# LTC6804-2_12S.net
KiCad netlist of a schematic drawn in Altium Designer
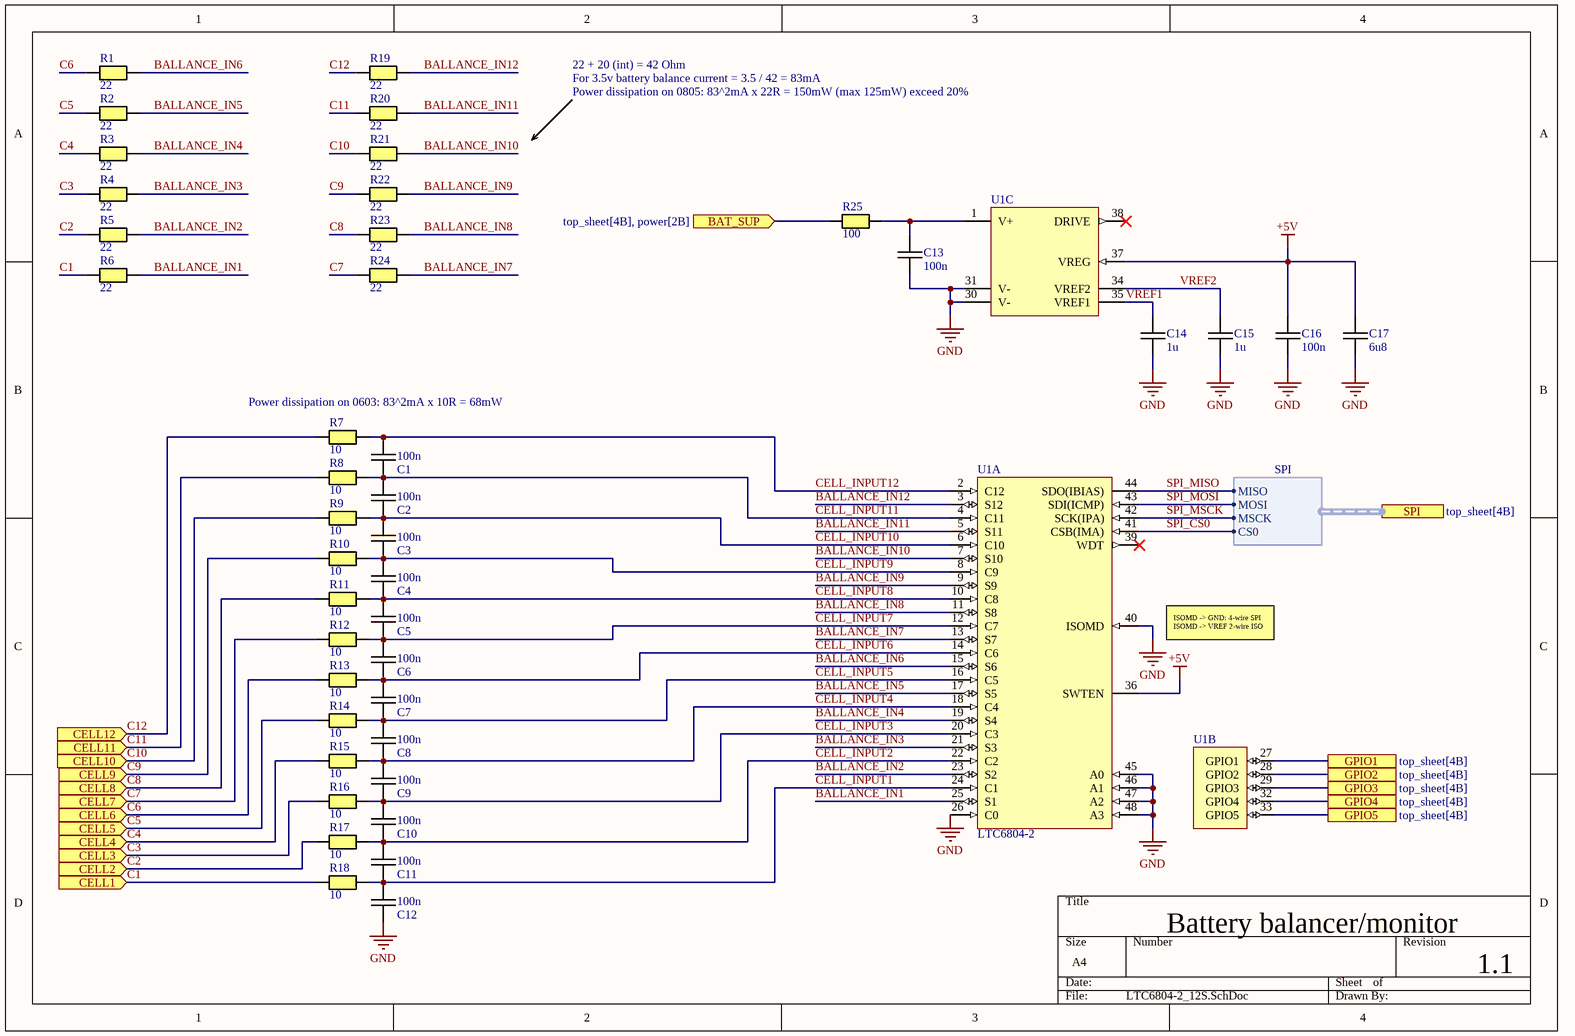
[diagram p0: LTC6804-2_12S.SchDoc]

(export (version "E")
  (design (tool "Eeschema 10.0.6"))
  (components
    (comp (ref "C1")
      (value "100n")
      (footprint "CAPC0603(1608)55_N")
      (description "Ceramic capacitor Medium density")
      (libsource (lib "Discrete") (part "Capacitor M"))
    )
    (comp (ref "C2")
      (value "100n")
      (footprint "CAPC0603(1608)55_N")
      (description "Ceramic capacitor Medium density")
      (libsource (lib "Discrete") (part "Capacitor M"))
    )
    (comp (ref "C3")
      (value "100n")
      (footprint "CAPC0603(1608)55_N")
      (description "Ceramic capacitor Medium density")
      (libsource (lib "Discrete") (part "Capacitor M"))
    )
    (comp (ref "C4")
      (value "100n")
      (footprint "CAPC0603(1608)55_N")
      (description "Ceramic capacitor Medium density")
      (libsource (lib "Discrete") (part "Capacitor M"))
    )
    (comp (ref "C5")
      (value "100n")
      (footprint "CAPC0603(1608)55_N")
      (description "Ceramic capacitor Medium density")
      (libsource (lib "Discrete") (part "Capacitor M"))
    )
    (comp (ref "C6")
      (value "100n")
      (footprint "CAPC0603(1608)55_N")
      (description "Ceramic capacitor Medium density")
      (libsource (lib "Discrete") (part "Capacitor M"))
    )
    (comp (ref "C7")
      (value "100n")
      (footprint "CAPC0603(1608)55_N")
      (description "Ceramic capacitor Medium density")
      (libsource (lib "Discrete") (part "Capacitor M"))
    )
    (comp (ref "C8")
      (value "100n")
      (footprint "CAPC0603(1608)55_N")
      (description "Ceramic capacitor Medium density")
      (libsource (lib "Discrete") (part "Capacitor M"))
    )
    (comp (ref "C9")
      (value "100n")
      (footprint "CAPC0603(1608)55_N")
      (description "Ceramic capacitor Medium density")
      (libsource (lib "Discrete") (part "Capacitor M"))
    )
    (comp (ref "C10")
      (value "100n")
      (footprint "CAPC0603(1608)55_N")
      (description "Ceramic capacitor Medium density")
      (libsource (lib "Discrete") (part "Capacitor M"))
    )
    (comp (ref "C11")
      (value "100n")
      (footprint "CAPC0603(1608)55_N")
      (description "Ceramic capacitor Medium density")
      (libsource (lib "Discrete") (part "Capacitor M"))
    )
    (comp (ref "C12")
      (value "100n")
      (footprint "CAPC0603(1608)55_N")
      (description "Ceramic capacitor Medium density")
      (libsource (lib "Discrete") (part "Capacitor M"))
    )
    (comp (ref "C13")
      (value "100n")
      (footprint "CAPC0603(1608)55_N")
      (description "Ceramic capacitor Medium density")
      (libsource (lib "Discrete") (part "Capacitor M"))
    )
    (comp (ref "C14")
      (value "1u")
      (footprint "CAPC0805(2012)75_N")
      (description "Ceramic capacitor Medium density")
      (libsource (lib "Discrete") (part "Capacitor M"))
    )
    (comp (ref "C15")
      (value "1u")
      (footprint "CAPC0805(2012)75_N")
      (description "Ceramic capacitor Medium density")
      (libsource (lib "Discrete") (part "Capacitor M"))
    )
    (comp (ref "C16")
      (value "100n")
      (footprint "CAPC0603(1608)55_N")
      (description "Ceramic capacitor Medium density")
      (libsource (lib "Discrete") (part "Capacitor M"))
    )
    (comp (ref "C17")
      (value "6u8")
      (footprint "CAPC0805(2012)75_N")
      (description "Ceramic capacitor Medium density")
      (libsource (lib "Discrete") (part "Capacitor M"))
    )
    (comp (ref "R1")
      (value "22")
      (footprint "RESC0805(2012)_N")
      (description "Resistor Medium Density")
      (libsource (lib "Discrete") (part "Resistor M"))
    )
    (comp (ref "R2")
      (value "22")
      (footprint "RESC0805(2012)_N")
      (description "Resistor Medium Density")
      (libsource (lib "Discrete") (part "Resistor M"))
    )
    (comp (ref "R3")
      (value "22")
      (footprint "RESC0805(2012)_N")
      (description "Resistor Medium Density")
      (libsource (lib "Discrete") (part "Resistor M"))
    )
    (comp (ref "R4")
      (value "22")
      (footprint "RESC0805(2012)_N")
      (description "Resistor Medium Density")
      (libsource (lib "Discrete") (part "Resistor M"))
    )
    (comp (ref "R5")
      (value "22")
      (footprint "RESC0805(2012)_N")
      (description "Resistor Medium Density")
      (libsource (lib "Discrete") (part "Resistor M"))
    )
    (comp (ref "R6")
      (value "22")
      (footprint "RESC0805(2012)_N")
      (description "Resistor Medium Density")
      (libsource (lib "Discrete") (part "Resistor M"))
    )
    (comp (ref "R7")
      (value "10")
      (footprint "RESC0603(1608)_N")
      (description "Resistor Medium Density")
      (libsource (lib "Discrete") (part "Resistor M"))
    )
    (comp (ref "R8")
      (value "10")
      (footprint "RESC0603(1608)_N")
      (description "Resistor Medium Density")
      (libsource (lib "Discrete") (part "Resistor M"))
    )
    (comp (ref "R9")
      (value "10")
      (footprint "RESC0603(1608)_N")
      (description "Resistor Medium Density")
      (libsource (lib "Discrete") (part "Resistor M"))
    )
    (comp (ref "R10")
      (value "10")
      (footprint "RESC0603(1608)_N")
      (description "Resistor Medium Density")
      (libsource (lib "Discrete") (part "Resistor M"))
    )
    (comp (ref "R11")
      (value "10")
      (footprint "RESC0603(1608)_N")
      (description "Resistor Medium Density")
      (libsource (lib "Discrete") (part "Resistor M"))
    )
    (comp (ref "R12")
      (value "10")
      (footprint "RESC0603(1608)_N")
      (description "Resistor Medium Density")
      (libsource (lib "Discrete") (part "Resistor M"))
    )
    (comp (ref "R13")
      (value "10")
      (footprint "RESC0603(1608)_N")
      (description "Resistor Medium Density")
      (libsource (lib "Discrete") (part "Resistor M"))
    )
    (comp (ref "R14")
      (value "10")
      (footprint "RESC0603(1608)_N")
      (description "Resistor Medium Density")
      (libsource (lib "Discrete") (part "Resistor M"))
    )
    (comp (ref "R15")
      (value "10")
      (footprint "RESC0603(1608)_N")
      (description "Resistor Medium Density")
      (libsource (lib "Discrete") (part "Resistor M"))
    )
    (comp (ref "R16")
      (value "10")
      (footprint "RESC0603(1608)_N")
      (description "Resistor Medium Density")
      (libsource (lib "Discrete") (part "Resistor M"))
    )
    (comp (ref "R17")
      (value "10")
      (footprint "RESC0603(1608)_N")
      (description "Resistor Medium Density")
      (libsource (lib "Discrete") (part "Resistor M"))
    )
    (comp (ref "R18")
      (value "10")
      (footprint "RESC0603(1608)_N")
      (description "Resistor Medium Density")
      (libsource (lib "Discrete") (part "Resistor M"))
    )
    (comp (ref "R19")
      (value "22")
      (footprint "RESC0805(2012)_N")
      (description "Resistor Medium Density")
      (libsource (lib "Discrete") (part "Resistor M"))
    )
    (comp (ref "R20")
      (value "22")
      (footprint "RESC0805(2012)_N")
      (description "Resistor Medium Density")
      (libsource (lib "Discrete") (part "Resistor M"))
    )
    (comp (ref "R21")
      (value "22")
      (footprint "RESC0805(2012)_N")
      (description "Resistor Medium Density")
      (libsource (lib "Discrete") (part "Resistor M"))
    )
    (comp (ref "R22")
      (value "22")
      (footprint "RESC0805(2012)_N")
      (description "Resistor Medium Density")
      (libsource (lib "Discrete") (part "Resistor M"))
    )
    (comp (ref "R23")
      (value "22")
      (footprint "RESC0805(2012)_N")
      (description "Resistor Medium Density")
      (libsource (lib "Discrete") (part "Resistor M"))
    )
    (comp (ref "R24")
      (value "22")
      (footprint "RESC0805(2012)_N")
      (description "Resistor Medium Density")
      (libsource (lib "Discrete") (part "Resistor M"))
    )
    (comp (ref "R25")
      (value "100")
      (footprint "RESC0603(1608)_N")
      (description "Resistor Medium Density")
      (libsource (lib "Discrete") (part "Resistor M"))
    )
    (comp (ref "U1")
      (value "LTC6804-2")
      (footprint "SSOP48")
      (libsource (lib "IntegrationCircuits") (part "LTC6804-2"))
    )
  )
  (nets
    (net (code "2") (name "+5V") (class "Default")
      (node (ref "C16") (pin "1") (pinfunction "1_1") (pintype "passive"))
      (node (ref "C17") (pin "1") (pinfunction "1_1") (pintype "passive"))
      (node (ref "U1") (pin "36") (pinfunction "SWTEN_36") (pintype "passive"))
      (node (ref "U1") (pin "37") (pinfunction "VREG_37") (pintype "input"))
    )
    (net (code "3") (name "/BALLANCE_IN1") (class "Default")
      (node (ref "R6") (pin "2") (pinfunction "2_2") (pintype "passive"))
      (node (ref "U1") (pin "25") (pinfunction "S1_25") (pintype "bidirectional"))
    )
    (net (code "4") (name "/BALLANCE_IN2") (class "Default")
      (node (ref "R5") (pin "2") (pinfunction "2_2") (pintype "passive"))
      (node (ref "U1") (pin "23") (pinfunction "S2_23") (pintype "bidirectional"))
    )
    (net (code "5") (name "/BALLANCE_IN3") (class "Default")
      (node (ref "R4") (pin "2") (pinfunction "2_2") (pintype "passive"))
      (node (ref "U1") (pin "21") (pinfunction "S3_21") (pintype "bidirectional"))
    )
    (net (code "6") (name "/BALLANCE_IN4") (class "Default")
      (node (ref "R3") (pin "2") (pinfunction "2_2") (pintype "passive"))
      (node (ref "U1") (pin "19") (pinfunction "S4_19") (pintype "bidirectional"))
    )
    (net (code "7") (name "/BALLANCE_IN5") (class "Default")
      (node (ref "R2") (pin "2") (pinfunction "2_2") (pintype "passive"))
      (node (ref "U1") (pin "17") (pinfunction "S5_17") (pintype "bidirectional"))
    )
    (net (code "8") (name "/BALLANCE_IN6") (class "Default")
      (node (ref "R1") (pin "2") (pinfunction "2_2") (pintype "passive"))
      (node (ref "U1") (pin "15") (pinfunction "S6_15") (pintype "bidirectional"))
    )
    (net (code "9") (name "/BALLANCE_IN7") (class "Default")
      (node (ref "R24") (pin "2") (pinfunction "2_2") (pintype "passive"))
      (node (ref "U1") (pin "13") (pinfunction "S7_13") (pintype "bidirectional"))
    )
    (net (code "10") (name "/BALLANCE_IN8") (class "Default")
      (node (ref "R23") (pin "2") (pinfunction "2_2") (pintype "passive"))
      (node (ref "U1") (pin "11") (pinfunction "S8_11") (pintype "bidirectional"))
    )
    (net (code "11") (name "/BALLANCE_IN9") (class "Default")
      (node (ref "R22") (pin "2") (pinfunction "2_2") (pintype "passive"))
      (node (ref "U1") (pin "9") (pinfunction "S9_9") (pintype "bidirectional"))
    )
    (net (code "12") (name "/BALLANCE_IN10") (class "Default")
      (node (ref "R21") (pin "2") (pinfunction "2_2") (pintype "passive"))
      (node (ref "U1") (pin "7") (pinfunction "S10_7") (pintype "bidirectional"))
    )
    (net (code "13") (name "/BALLANCE_IN11") (class "Default")
      (node (ref "R20") (pin "2") (pinfunction "2_2") (pintype "passive"))
      (node (ref "U1") (pin "5") (pinfunction "S11_5") (pintype "bidirectional"))
    )
    (net (code "14") (name "/BALLANCE_IN12") (class "Default")
      (node (ref "R19") (pin "2") (pinfunction "2_2") (pintype "passive"))
      (node (ref "U1") (pin "3") (pinfunction "S12_3") (pintype "bidirectional"))
    )
    (net (code "15") (name "/BAT_SUP") (class "Default")
      (node (ref "R25") (pin "1") (pinfunction "1_1") (pintype "passive"))
    )
    (net (code "16") (name "/C1") (class "Default")
      (node (ref "R18") (pin "1") (pinfunction "1_1") (pintype "passive"))
      (node (ref "R6") (pin "1") (pinfunction "1_1") (pintype "passive"))
    )
    (net (code "17") (name "/C2") (class "Default")
      (node (ref "R17") (pin "1") (pinfunction "1_1") (pintype "passive"))
      (node (ref "R5") (pin "1") (pinfunction "1_1") (pintype "passive"))
    )
    (net (code "18") (name "/C3") (class "Default")
      (node (ref "R16") (pin "1") (pinfunction "1_1") (pintype "passive"))
      (node (ref "R4") (pin "1") (pinfunction "1_1") (pintype "passive"))
    )
    (net (code "19") (name "/C4") (class "Default")
      (node (ref "R15") (pin "1") (pinfunction "1_1") (pintype "passive"))
      (node (ref "R3") (pin "1") (pinfunction "1_1") (pintype "passive"))
    )
    (net (code "20") (name "/C5") (class "Default")
      (node (ref "R14") (pin "1") (pinfunction "1_1") (pintype "passive"))
      (node (ref "R2") (pin "1") (pinfunction "1_1") (pintype "passive"))
    )
    (net (code "21") (name "/C6") (class "Default")
      (node (ref "R1") (pin "1") (pinfunction "1_1") (pintype "passive"))
      (node (ref "R13") (pin "1") (pinfunction "1_1") (pintype "passive"))
    )
    (net (code "22") (name "/C7") (class "Default")
      (node (ref "R12") (pin "1") (pinfunction "1_1") (pintype "passive"))
      (node (ref "R24") (pin "1") (pinfunction "1_1") (pintype "passive"))
    )
    (net (code "23") (name "/C8") (class "Default")
      (node (ref "R11") (pin "1") (pinfunction "1_1") (pintype "passive"))
      (node (ref "R23") (pin "1") (pinfunction "1_1") (pintype "passive"))
    )
    (net (code "24") (name "/C9") (class "Default")
      (node (ref "R10") (pin "1") (pinfunction "1_1") (pintype "passive"))
      (node (ref "R22") (pin "1") (pinfunction "1_1") (pintype "passive"))
    )
    (net (code "25") (name "/C10") (class "Default")
      (node (ref "R21") (pin "1") (pinfunction "1_1") (pintype "passive"))
      (node (ref "R9") (pin "1") (pinfunction "1_1") (pintype "passive"))
    )
    (net (code "26") (name "/C11") (class "Default")
      (node (ref "R20") (pin "1") (pinfunction "1_1") (pintype "passive"))
      (node (ref "R8") (pin "1") (pinfunction "1_1") (pintype "passive"))
    )
    (net (code "27") (name "/C12") (class "Default")
      (node (ref "R19") (pin "1") (pinfunction "1_1") (pintype "passive"))
      (node (ref "R7") (pin "1") (pinfunction "1_1") (pintype "passive"))
    )
    (net (code "28") (name "/CELL_INPUT1") (class "Default")
      (node (ref "C11") (pin "2") (pinfunction "2_2") (pintype "passive"))
      (node (ref "C12") (pin "1") (pinfunction "1_1") (pintype "passive"))
      (node (ref "R18") (pin "2") (pinfunction "2_2") (pintype "passive"))
      (node (ref "U1") (pin "24") (pinfunction "C1_24") (pintype "input"))
    )
    (net (code "29") (name "/CELL_INPUT2") (class "Default")
      (node (ref "C10") (pin "2") (pinfunction "2_2") (pintype "passive"))
      (node (ref "C11") (pin "1") (pinfunction "1_1") (pintype "passive"))
      (node (ref "R17") (pin "2") (pinfunction "2_2") (pintype "passive"))
      (node (ref "U1") (pin "22") (pinfunction "C2_22") (pintype "input"))
    )
    (net (code "30") (name "/CELL_INPUT3") (class "Default")
      (node (ref "C10") (pin "1") (pinfunction "1_1") (pintype "passive"))
      (node (ref "C9") (pin "2") (pinfunction "2_2") (pintype "passive"))
      (node (ref "R16") (pin "2") (pinfunction "2_2") (pintype "passive"))
      (node (ref "U1") (pin "20") (pinfunction "C3_20") (pintype "input"))
    )
    (net (code "31") (name "/CELL_INPUT4") (class "Default")
      (node (ref "C8") (pin "2") (pinfunction "2_2") (pintype "passive"))
      (node (ref "C9") (pin "1") (pinfunction "1_1") (pintype "passive"))
      (node (ref "R15") (pin "2") (pinfunction "2_2") (pintype "passive"))
      (node (ref "U1") (pin "18") (pinfunction "C4_18") (pintype "input"))
    )
    (net (code "32") (name "/CELL_INPUT5") (class "Default")
      (node (ref "C7") (pin "2") (pinfunction "2_2") (pintype "passive"))
      (node (ref "C8") (pin "1") (pinfunction "1_1") (pintype "passive"))
      (node (ref "R14") (pin "2") (pinfunction "2_2") (pintype "passive"))
      (node (ref "U1") (pin "16") (pinfunction "C5_16") (pintype "input"))
    )
    (net (code "33") (name "/CELL_INPUT6") (class "Default")
      (node (ref "C6") (pin "2") (pinfunction "2_2") (pintype "passive"))
      (node (ref "C7") (pin "1") (pinfunction "1_1") (pintype "passive"))
      (node (ref "R13") (pin "2") (pinfunction "2_2") (pintype "passive"))
      (node (ref "U1") (pin "14") (pinfunction "C6_14") (pintype "input"))
    )
    (net (code "34") (name "/CELL_INPUT7") (class "Default")
      (node (ref "C5") (pin "2") (pinfunction "2_2") (pintype "passive"))
      (node (ref "C6") (pin "1") (pinfunction "1_1") (pintype "passive"))
      (node (ref "R12") (pin "2") (pinfunction "2_2") (pintype "passive"))
      (node (ref "U1") (pin "12") (pinfunction "C7_12") (pintype "input"))
    )
    (net (code "35") (name "/CELL_INPUT8") (class "Default")
      (node (ref "C4") (pin "2") (pinfunction "2_2") (pintype "passive"))
      (node (ref "C5") (pin "1") (pinfunction "1_1") (pintype "passive"))
      (node (ref "R11") (pin "2") (pinfunction "2_2") (pintype "passive"))
      (node (ref "U1") (pin "10") (pinfunction "C8_10") (pintype "input"))
    )
    (net (code "36") (name "/CELL_INPUT9") (class "Default")
      (node (ref "C3") (pin "2") (pinfunction "2_2") (pintype "passive"))
      (node (ref "C4") (pin "1") (pinfunction "1_1") (pintype "passive"))
      (node (ref "R10") (pin "2") (pinfunction "2_2") (pintype "passive"))
      (node (ref "U1") (pin "8") (pinfunction "C9_8") (pintype "input"))
    )
    (net (code "37") (name "/CELL_INPUT10") (class "Default")
      (node (ref "C2") (pin "2") (pinfunction "2_2") (pintype "passive"))
      (node (ref "C3") (pin "1") (pinfunction "1_1") (pintype "passive"))
      (node (ref "R9") (pin "2") (pinfunction "2_2") (pintype "passive"))
      (node (ref "U1") (pin "6") (pinfunction "C10_6") (pintype "input"))
    )
    (net (code "38") (name "/CELL_INPUT11") (class "Default")
      (node (ref "C1") (pin "2") (pinfunction "2_2") (pintype "passive"))
      (node (ref "C2") (pin "1") (pinfunction "1_1") (pintype "passive"))
      (node (ref "R8") (pin "2") (pinfunction "2_2") (pintype "passive"))
      (node (ref "U1") (pin "4") (pinfunction "C11_4") (pintype "input"))
    )
    (net (code "39") (name "/CELL_INPUT12") (class "Default")
      (node (ref "C1") (pin "1") (pinfunction "1_1") (pintype "passive"))
      (node (ref "R7") (pin "2") (pinfunction "2_2") (pintype "passive"))
      (node (ref "U1") (pin "2") (pinfunction "C12_2") (pintype "input"))
    )
    (net (code "40") (name "/GPIO1") (class "Default")
      (node (ref "U1") (pin "27") (pinfunction "GPIO1_27") (pintype "bidirectional"))
    )
    (net (code "41") (name "/GPIO2") (class "Default")
      (node (ref "U1") (pin "28") (pinfunction "GPIO2_28") (pintype "bidirectional"))
    )
    (net (code "42") (name "/GPIO3") (class "Default")
      (node (ref "U1") (pin "29") (pinfunction "GPIO3_29") (pintype "bidirectional"))
    )
    (net (code "43") (name "/GPIO4") (class "Default")
      (node (ref "U1") (pin "32") (pinfunction "GPIO4_32") (pintype "bidirectional"))
    )
    (net (code "44") (name "/GPIO5") (class "Default")
      (node (ref "U1") (pin "33") (pinfunction "GPIO5_33") (pintype "bidirectional"))
    )
    (net (code "45") (name "/SPI_CS0") (class "Default")
      (node (ref "U1") (pin "41") (pinfunction "CSB(IMA)_41") (pintype "input"))
    )
    (net (code "46") (name "/SPI_MISO") (class "Default")
      (node (ref "U1") (pin "44") (pinfunction "SDO(IBIAS)_44") (pintype "open_collector"))
    )
    (net (code "47") (name "/SPI_MOSI") (class "Default")
      (node (ref "U1") (pin "43") (pinfunction "SDI(ICMP)_43") (pintype "input"))
    )
    (net (code "48") (name "/SPI_MSCK") (class "Default")
      (node (ref "U1") (pin "42") (pinfunction "SCK(IPA)_42") (pintype "input"))
    )
    (net (code "49") (name "/VREF1") (class "Default")
      (node (ref "C14") (pin "1") (pinfunction "1_1") (pintype "passive"))
      (node (ref "U1") (pin "35") (pinfunction "VREF1_35") (pintype "power_in"))
    )
    (net (code "50") (name "/VREF2") (class "Default")
      (node (ref "C15") (pin "1") (pinfunction "1_1") (pintype "passive"))
      (node (ref "U1") (pin "34") (pinfunction "VREF2_34") (pintype "power_in"))
    )
    (net (code "52") (name "GND") (class "Default")
      (node (ref "C12") (pin "2") (pinfunction "2_2") (pintype "passive"))
      (node (ref "C13") (pin "2") (pinfunction "2_2") (pintype "passive"))
      (node (ref "C14") (pin "2") (pinfunction "2_2") (pintype "passive"))
      (node (ref "C15") (pin "2") (pinfunction "2_2") (pintype "passive"))
      (node (ref "C16") (pin "2") (pinfunction "2_2") (pintype "passive"))
      (node (ref "C17") (pin "2") (pinfunction "2_2") (pintype "passive"))
      (node (ref "U1") (pin "26") (pinfunction "C0_26") (pintype "input"))
      (node (ref "U1") (pin "30") (pinfunction "V-_30") (pintype "power_in"))
      (node (ref "U1") (pin "31") (pinfunction "V-_31") (pintype "power_in"))
      (node (ref "U1") (pin "40") (pinfunction "ISOMD_40") (pintype "input"))
      (node (ref "U1") (pin "45") (pinfunction "A0_45") (pintype "input"))
      (node (ref "U1") (pin "46") (pinfunction "A1_46") (pintype "input"))
      (node (ref "U1") (pin "47") (pinfunction "A2_47") (pintype "input"))
      (node (ref "U1") (pin "48") (pinfunction "A3_48") (pintype "input"))
    )
    (net (code "53") (name "Net-(U1C-V+)") (class "Default")
      (node (ref "C13") (pin "1") (pinfunction "1_1") (pintype "passive"))
      (node (ref "R25") (pin "2") (pinfunction "2_2") (pintype "passive"))
      (node (ref "U1") (pin "1") (pinfunction "V+_1") (pintype "power_in"))
    )
    (net (code "54") (name "unconnected-(U1A-WDT-Pad39)") (class "Default")
      (node (ref "U1") (pin "39") (pinfunction "WDT_39") (pintype "output+no_connect"))
    )
    (net (code "55") (name "unconnected-(U1C-DRIVE-Pad38)") (class "Default")
      (node (ref "U1") (pin "38") (pinfunction "DRIVE_38") (pintype "output+no_connect"))
    )
  )
)
